# Mea_Vox_1_0a.net
KiCad netlist of a schematic drawn in EAGLE
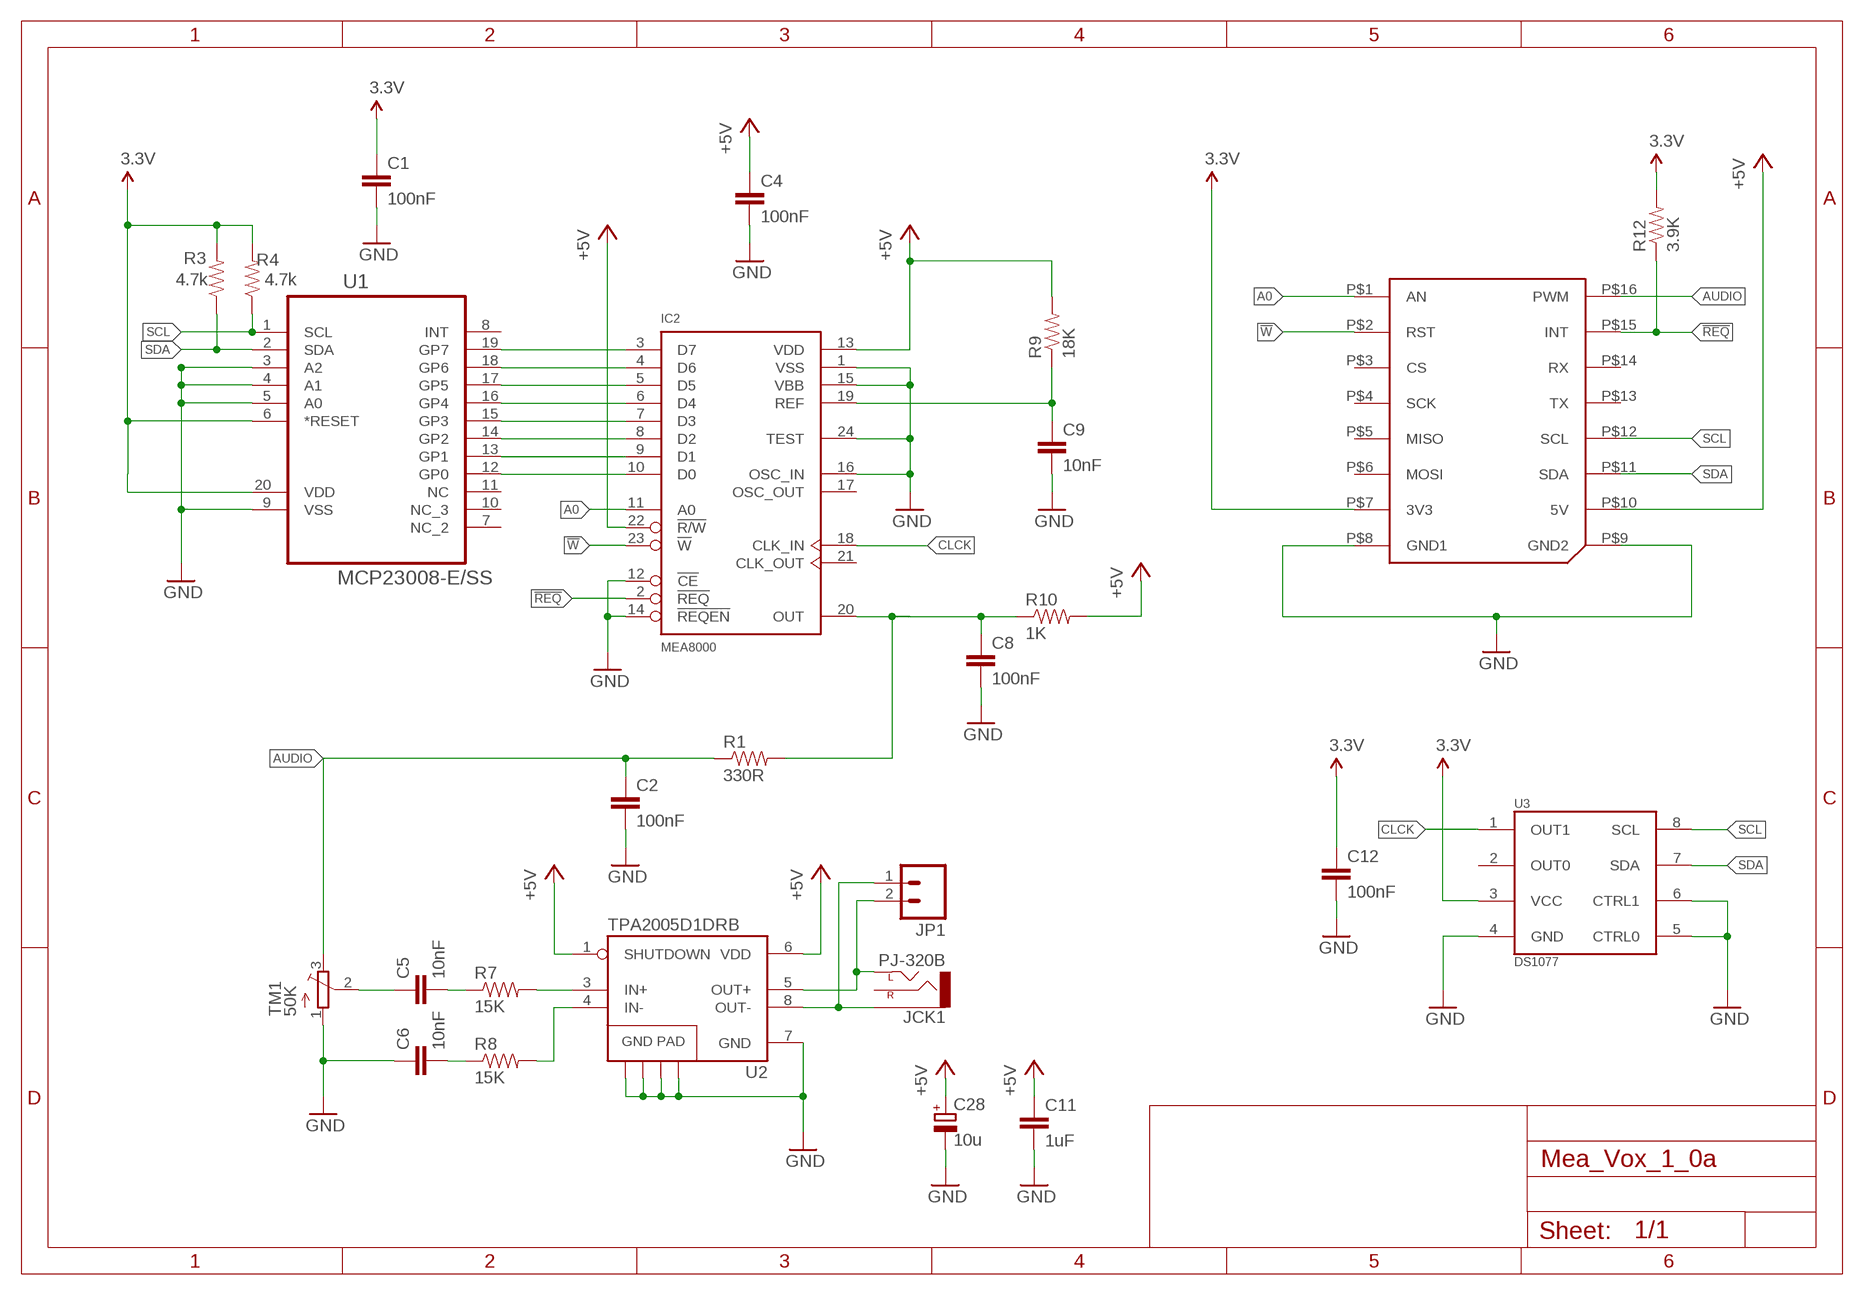
[diagram p0: schematic, sheet 1]

(export (version "E")
  (design (tool "Eeschema 10.0.6"))
  (components
    (comp (ref "C1")
      (value "100nF")
      (footprint "eagle-import:SPARKFUN_0805")
      (libsource (lib "eagle-import") (part "SPARKFUN_CAP0805"))
    )
    (comp (ref "C2")
      (value "100nF")
      (footprint "eagle-import:SPARKFUN_0805")
      (libsource (lib "eagle-import") (part "SPARKFUN_CAP0805"))
    )
    (comp (ref "C4")
      (value "100nF")
      (footprint "eagle-import:SPARKFUN_0805")
      (libsource (lib "eagle-import") (part "SPARKFUN_CAP0805"))
    )
    (comp (ref "C5")
      (value "10nF")
      (footprint "eagle-import:SPARKFUN_0805")
      (libsource (lib "eagle-import") (part "SPARKFUN_CAP0805"))
    )
    (comp (ref "C6")
      (value "10nF")
      (footprint "eagle-import:SPARKFUN_0805")
      (libsource (lib "eagle-import") (part "SPARKFUN_CAP0805"))
    )
    (comp (ref "C8")
      (value "100nF")
      (footprint "eagle-import:SPARKFUN_0805")
      (libsource (lib "eagle-import") (part "SPARKFUN_CAP0805"))
    )
    (comp (ref "C9")
      (value "10nF")
      (footprint "eagle-import:SPARKFUN_0805")
      (libsource (lib "eagle-import") (part "SPARKFUN_CAP0805"))
    )
    (comp (ref "C11")
      (value "1uF")
      (footprint "eagle-import:SPARKFUN_0805")
      (libsource (lib "eagle-import") (part "SPARKFUN_CAP0805"))
    )
    (comp (ref "C12")
      (value "100nF")
      (footprint "eagle-import:SPARKFUN_0805")
      (libsource (lib "eagle-import") (part "SPARKFUN_CAP0805"))
    )
    (comp (ref "C28")
      (value "10u")
      (footprint "eagle-import:A_3216-18R")
      (libsource (lib "eagle-import") (part "CPOL-EUA/3216-18R"))
    )
    (comp (ref "IC2")
      (value "MEA8000")
      (footprint "eagle-import:DIL24-6")
      (libsource (lib "eagle-import") (part "MEA8000"))
    )
    (comp (ref "JCK1")
      (value "PJ-320B")
      (footprint "eagle-import:FOOTPRINT")
      (libsource (lib "eagle-import") (part "PJ-320B"))
    )
    (comp (ref "JP1")
      (value "M02PTH")
      (footprint "eagle-import:1X02")
      (libsource (lib "eagle-import") (part "M02PTH"))
    )
    (comp (ref "MK1")
      (value "MIKROE_CLICKLARGE")
      (footprint "eagle-import:MIKROE_BUS_LARGE")
      (libsource (lib "eagle-import") (part "MIKROE_CLICKLARGE"))
    )
    (comp (ref "R1")
      (value "330R")
      (footprint "eagle-import:SPARKFUN_0805")
      (libsource (lib "eagle-import") (part "SPARKFUN_RESISTOR0805-RES"))
    )
    (comp (ref "R3")
      (value "4.7k")
      (footprint "eagle-import:SPARKFUN_0805")
      (libsource (lib "eagle-import") (part "SPARKFUN_RESISTOR0805-RES"))
    )
    (comp (ref "R4")
      (value "4.7k")
      (footprint "eagle-import:SPARKFUN_0805")
      (libsource (lib "eagle-import") (part "SPARKFUN_RESISTOR0805-RES"))
    )
    (comp (ref "R7")
      (value "15K")
      (footprint "eagle-import:SPARKFUN_0805")
      (libsource (lib "eagle-import") (part "SPARKFUN_RESISTOR0805-RES"))
    )
    (comp (ref "R8")
      (value "15K")
      (footprint "eagle-import:SPARKFUN_0805")
      (libsource (lib "eagle-import") (part "SPARKFUN_RESISTOR0805-RES"))
    )
    (comp (ref "R9")
      (value "18K")
      (footprint "eagle-import:SPARKFUN_0805")
      (libsource (lib "eagle-import") (part "SPARKFUN_RESISTOR0805-RES"))
    )
    (comp (ref "R10")
      (value "1K")
      (footprint "eagle-import:SPARKFUN_0805")
      (libsource (lib "eagle-import") (part "SPARKFUN_RESISTOR0805-RES"))
    )
    (comp (ref "R12")
      (value "3.9K")
      (footprint "eagle-import:SPARKFUN_0805")
      (libsource (lib "eagle-import") (part "SPARKFUN_RESISTOR0805-RES"))
    )
    (comp (ref "TM1")
      (value "50K")
      (footprint "eagle-import:TC33X")
      (libsource (lib "eagle-import") (part "TRIMPOTTC33X"))
    )
    (comp (ref "U1")
      (value "MCP23008-E/SS")
      (footprint "eagle-import:SOP65P780X200-20N")
      (libsource (lib "eagle-import") (part "MCP23008-E/SS"))
    )
    (comp (ref "U2")
      (value "TPA2005D1DRB")
      (footprint "eagle-import:QFN-8_PAD")
      (libsource (lib "eagle-import") (part "TPA2005D1DRB"))
    )
    (comp (ref "U3")
      (value "DS1077")
      (footprint "eagle-import:SO08")
      (libsource (lib "eagle-import") (part "DS1077"))
    )
  )
  (nets
    (net (code "1") (name "+5V") (class "Default")
      (node (ref "C11") (pin "1") (pinfunction "1_1") (pintype "passive"))
      (node (ref "C28") (pin "+") (pinfunction "+_+") (pintype "passive"))
      (node (ref "C4") (pin "1") (pinfunction "1_1") (pintype "passive"))
      (node (ref "IC2") (pin "13") (pinfunction "VDD_13") (pintype "power_in"))
      (node (ref "IC2") (pin "22") (pinfunction "~{R/W}_22") (pintype "input"))
      (node (ref "MK1") (pin "P$10") (pinfunction "5V_P$10") (pintype "bidirectional"))
      (node (ref "R10") (pin "2") (pinfunction "2_2") (pintype "passive"))
      (node (ref "R9") (pin "2") (pinfunction "2_2") (pintype "passive"))
      (node (ref "U2") (pin "1") (pinfunction "SHUTDOWN_1") (pintype "input"))
      (node (ref "U2") (pin "6") (pinfunction "VDD_6") (pintype "power_in"))
    )
    (net (code "2") (name "/~{REQ}") (class "Default")
      (node (ref "IC2") (pin "2") (pinfunction "~{REQ}_2") (pintype "input"))
      (node (ref "MK1") (pin "P$15") (pinfunction "INT_P$15") (pintype "bidirectional"))
      (node (ref "R12") (pin "1") (pinfunction "1_1") (pintype "passive"))
    )
    (net (code "3") (name "/~{W}") (class "Default")
      (node (ref "IC2") (pin "23") (pinfunction "~{W}_23") (pintype "input"))
      (node (ref "MK1") (pin "P$2") (pinfunction "RST_P$2") (pintype "bidirectional"))
    )
    (net (code "4") (name "3.3V") (class "Default")
      (node (ref "C1") (pin "1") (pinfunction "1_1") (pintype "passive"))
      (node (ref "C12") (pin "1") (pinfunction "1_1") (pintype "passive"))
      (node (ref "MK1") (pin "P$7") (pinfunction "3V3_P$7") (pintype "bidirectional"))
      (node (ref "R12") (pin "2") (pinfunction "2_2") (pintype "passive"))
      (node (ref "R3") (pin "2") (pinfunction "2_2") (pintype "passive"))
      (node (ref "R4") (pin "2") (pinfunction "2_2") (pintype "passive"))
      (node (ref "U1") (pin "20") (pinfunction "VDD_20") (pintype "power_in"))
      (node (ref "U1") (pin "6") (pinfunction "*RESET_6") (pintype "input"))
      (node (ref "U3") (pin "3") (pinfunction "VCC_3") (pintype "bidirectional"))
    )
    (net (code "5") (name "A0") (class "Default")
      (node (ref "IC2") (pin "11") (pinfunction "A0_11") (pintype "input"))
      (node (ref "MK1") (pin "P$1") (pinfunction "AN_P$1") (pintype "bidirectional"))
    )
    (net (code "6") (name "AUDIO") (class "Default")
      (node (ref "C2") (pin "1") (pinfunction "1_1") (pintype "passive"))
      (node (ref "MK1") (pin "P$16") (pinfunction "PWM_P$16") (pintype "bidirectional"))
      (node (ref "R1") (pin "1") (pinfunction "1_1") (pintype "passive"))
      (node (ref "TM1") (pin "3") (pinfunction "E_3") (pintype "passive"))
    )
    (net (code "7") (name "CLCK") (class "Default")
      (node (ref "IC2") (pin "18") (pinfunction "CLK_IN_18") (pintype "input"))
      (node (ref "U3") (pin "1") (pinfunction "OUT1_1") (pintype "bidirectional"))
    )
    (net (code "8") (name "GND") (class "Default")
      (node (ref "C1") (pin "2") (pinfunction "2_2") (pintype "passive"))
      (node (ref "C11") (pin "2") (pinfunction "2_2") (pintype "passive"))
      (node (ref "C12") (pin "2") (pinfunction "2_2") (pintype "passive"))
      (node (ref "C2") (pin "2") (pinfunction "2_2") (pintype "passive"))
      (node (ref "C28") (pin "-") (pinfunction "-_-") (pintype "passive"))
      (node (ref "C4") (pin "2") (pinfunction "2_2") (pintype "passive"))
      (node (ref "C6") (pin "1") (pinfunction "1_1") (pintype "passive"))
      (node (ref "C8") (pin "2") (pinfunction "2_2") (pintype "passive"))
      (node (ref "C9") (pin "2") (pinfunction "2_2") (pintype "passive"))
      (node (ref "IC2") (pin "1") (pinfunction "VSS_1") (pintype "power_in"))
      (node (ref "IC2") (pin "12") (pinfunction "~{CE}_12") (pintype "input"))
      (node (ref "IC2") (pin "14") (pinfunction "~{REQEN}_14") (pintype "input"))
      (node (ref "IC2") (pin "15") (pinfunction "VBB_15") (pintype "power_in"))
      (node (ref "IC2") (pin "16") (pinfunction "OSC_IN_16") (pintype "input"))
      (node (ref "IC2") (pin "24") (pinfunction "TEST_24") (pintype "bidirectional"))
      (node (ref "MK1") (pin "P$8") (pinfunction "GND1_P$8") (pintype "bidirectional"))
      (node (ref "MK1") (pin "P$9") (pinfunction "GND2_P$9") (pintype "bidirectional"))
      (node (ref "TM1") (pin "1") (pinfunction "A_1") (pintype "passive"))
      (node (ref "U1") (pin "3") (pinfunction "A2_3") (pintype "bidirectional"))
      (node (ref "U1") (pin "4") (pinfunction "A1_4") (pintype "input"))
      (node (ref "U1") (pin "5") (pinfunction "A0_5") (pintype "input"))
      (node (ref "U1") (pin "9") (pinfunction "VSS_9") (pintype "passive"))
      (node (ref "U2") (pin "10") (pinfunction "GND_10") (pintype "power_in"))
      (node (ref "U2") (pin "11") (pinfunction "GND_11") (pintype "power_in"))
      (node (ref "U2") (pin "12") (pinfunction "GND_12") (pintype "bidirectional"))
      (node (ref "U2") (pin "13") (pinfunction "GND_13") (pintype "bidirectional"))
      (node (ref "U2") (pin "7") (pinfunction "GND_7") (pintype "power_in"))
      (node (ref "U3") (pin "4") (pinfunction "GND_4") (pintype "bidirectional"))
      (node (ref "U3") (pin "5") (pinfunction "CTRL0_5") (pintype "bidirectional"))
      (node (ref "U3") (pin "6") (pinfunction "CTRL1_6") (pintype "bidirectional"))
    )
    (net (code "9") (name "Net-(C5-Pad2)") (class "Default")
      (node (ref "C5") (pin "2") (pinfunction "2_2") (pintype "passive"))
      (node (ref "R7") (pin "1") (pinfunction "1_1") (pintype "passive"))
    )
    (net (code "10") (name "Net-(C6-Pad2)") (class "Default")
      (node (ref "C6") (pin "2") (pinfunction "2_2") (pintype "passive"))
      (node (ref "R8") (pin "1") (pinfunction "1_1") (pintype "passive"))
    )
    (net (code "11") (name "Net-(IC2-D0)") (class "Default")
      (node (ref "IC2") (pin "10") (pinfunction "D0_10") (pintype "input"))
      (node (ref "U1") (pin "12") (pinfunction "GP0_12") (pintype "bidirectional"))
    )
    (net (code "12") (name "Net-(IC2-D1)") (class "Default")
      (node (ref "IC2") (pin "9") (pinfunction "D1_9") (pintype "input"))
      (node (ref "U1") (pin "13") (pinfunction "GP1_13") (pintype "bidirectional"))
    )
    (net (code "13") (name "Net-(IC2-D2)") (class "Default")
      (node (ref "IC2") (pin "8") (pinfunction "D2_8") (pintype "input"))
      (node (ref "U1") (pin "14") (pinfunction "GP2_14") (pintype "bidirectional"))
    )
    (net (code "14") (name "Net-(IC2-D3)") (class "Default")
      (node (ref "IC2") (pin "7") (pinfunction "D3_7") (pintype "input"))
      (node (ref "U1") (pin "15") (pinfunction "GP3_15") (pintype "bidirectional"))
    )
    (net (code "15") (name "Net-(IC2-D4)") (class "Default")
      (node (ref "IC2") (pin "6") (pinfunction "D4_6") (pintype "input"))
      (node (ref "U1") (pin "16") (pinfunction "GP4_16") (pintype "bidirectional"))
    )
    (net (code "16") (name "Net-(IC2-D5)") (class "Default")
      (node (ref "IC2") (pin "5") (pinfunction "D5_5") (pintype "input"))
      (node (ref "U1") (pin "17") (pinfunction "GP5_17") (pintype "bidirectional"))
    )
    (net (code "17") (name "Net-(IC2-D6)") (class "Default")
      (node (ref "IC2") (pin "4") (pinfunction "D6_4") (pintype "input"))
      (node (ref "U1") (pin "18") (pinfunction "GP6_18") (pintype "bidirectional"))
    )
    (net (code "18") (name "Net-(IC2-D7)") (class "Default")
      (node (ref "IC2") (pin "3") (pinfunction "D7_3") (pintype "input"))
      (node (ref "U1") (pin "19") (pinfunction "GP7_19") (pintype "bidirectional"))
    )
    (net (code "19") (name "Net-(IC2-OUT)") (class "Default")
      (node (ref "C8") (pin "1") (pinfunction "1_1") (pintype "passive"))
      (node (ref "IC2") (pin "20") (pinfunction "OUT_20") (pintype "output"))
      (node (ref "R1") (pin "2") (pinfunction "2_2") (pintype "passive"))
      (node (ref "R10") (pin "1") (pinfunction "1_1") (pintype "passive"))
    )
    (net (code "20") (name "Net-(IC2-REF)") (class "Default")
      (node (ref "C9") (pin "1") (pinfunction "1_1") (pintype "passive"))
      (node (ref "IC2") (pin "19") (pinfunction "REF_19") (pintype "input"))
      (node (ref "R9") (pin "1") (pinfunction "1_1") (pintype "passive"))
    )
    (net (code "21") (name "Net-(JCK1-LEFT)") (class "Default")
      (node (ref "JCK1") (pin "2") (pinfunction "LEFT_2") (pintype "bidirectional"))
      (node (ref "JP1") (pin "2") (pinfunction "2_2") (pintype "passive"))
      (node (ref "U2") (pin "5") (pinfunction "OUT+_5") (pintype "bidirectional"))
    )
    (net (code "22") (name "Net-(JCK1-SLEEVE)") (class "Default")
      (node (ref "JCK1") (pin "4") (pinfunction "SLEEVE_4") (pintype "bidirectional"))
      (node (ref "JP1") (pin "1") (pinfunction "1_1") (pintype "passive"))
      (node (ref "U2") (pin "8") (pinfunction "OUT-_8") (pintype "bidirectional"))
    )
    (net (code "23") (name "Net-(TM1-S)") (class "Default")
      (node (ref "C5") (pin "1") (pinfunction "1_1") (pintype "passive"))
      (node (ref "TM1") (pin "2") (pinfunction "S_2") (pintype "passive"))
    )
    (net (code "24") (name "Net-(U2-IN+)") (class "Default")
      (node (ref "R7") (pin "2") (pinfunction "2_2") (pintype "passive"))
      (node (ref "U2") (pin "3") (pinfunction "IN+_3") (pintype "bidirectional"))
    )
    (net (code "25") (name "Net-(U2-IN-)") (class "Default")
      (node (ref "R8") (pin "2") (pinfunction "2_2") (pintype "passive"))
      (node (ref "U2") (pin "4") (pinfunction "IN-_4") (pintype "bidirectional"))
    )
    (net (code "26") (name "SCL") (class "Default")
      (node (ref "MK1") (pin "P$12") (pinfunction "SCL_P$12") (pintype "bidirectional"))
      (node (ref "R4") (pin "1") (pinfunction "1_1") (pintype "passive"))
      (node (ref "U1") (pin "1") (pinfunction "SCL_1") (pintype "input"))
      (node (ref "U3") (pin "8") (pinfunction "SCL_8") (pintype "bidirectional"))
    )
    (net (code "27") (name "SDA") (class "Default")
      (node (ref "MK1") (pin "P$11") (pinfunction "SDA_P$11") (pintype "bidirectional"))
      (node (ref "R3") (pin "1") (pinfunction "1_1") (pintype "passive"))
      (node (ref "U1") (pin "2") (pinfunction "SDA_2") (pintype "bidirectional"))
      (node (ref "U3") (pin "7") (pinfunction "SDA_7") (pintype "bidirectional"))
    )
    (net (code "28") (name "unconnected-(IC2-CLK_OUT-Pad21)") (class "Default")
      (node (ref "IC2") (pin "21") (pinfunction "CLK_OUT_21") (pintype "output"))
    )
    (net (code "29") (name "unconnected-(IC2-OSC_OUT-Pad17)") (class "Default")
      (node (ref "IC2") (pin "17") (pinfunction "OSC_OUT_17") (pintype "output"))
    )
    (net (code "30") (name "unconnected-(JCK1-RIGHT-Pad3)") (class "Default")
      (node (ref "JCK1") (pin "3") (pinfunction "RIGHT_3") (pintype "bidirectional"))
    )
    (net (code "31") (name "unconnected-(MK1-CS-PadP$3)") (class "Default")
      (node (ref "MK1") (pin "P$3") (pinfunction "CS_P$3") (pintype "bidirectional"))
    )
    (net (code "32") (name "unconnected-(MK1-MISO-PadP$5)") (class "Default")
      (node (ref "MK1") (pin "P$5") (pinfunction "MISO_P$5") (pintype "bidirectional"))
    )
    (net (code "33") (name "unconnected-(MK1-MOSI-PadP$6)") (class "Default")
      (node (ref "MK1") (pin "P$6") (pinfunction "MOSI_P$6") (pintype "bidirectional"))
    )
    (net (code "34") (name "unconnected-(MK1-RX-PadP$14)") (class "Default")
      (node (ref "MK1") (pin "P$14") (pinfunction "RX_P$14") (pintype "bidirectional"))
    )
    (net (code "35") (name "unconnected-(MK1-SCK-PadP$4)") (class "Default")
      (node (ref "MK1") (pin "P$4") (pinfunction "SCK_P$4") (pintype "bidirectional"))
    )
    (net (code "36") (name "unconnected-(MK1-TX-PadP$13)") (class "Default")
      (node (ref "MK1") (pin "P$13") (pinfunction "TX_P$13") (pintype "bidirectional"))
    )
    (net (code "37") (name "unconnected-(U1-INT-Pad8)") (class "Default")
      (node (ref "U1") (pin "8") (pinfunction "INT_8") (pintype "output"))
    )
    (net (code "38") (name "unconnected-(U1-NC-Pad11)") (class "Default")
      (node (ref "U1") (pin "11") (pinfunction "NC_11") (pintype "no_connect"))
    )
    (net (code "39") (name "unconnected-(U1-NC_2-Pad7)") (class "Default")
      (node (ref "U1") (pin "7") (pinfunction "NC_2_7") (pintype "input"))
    )
    (net (code "40") (name "unconnected-(U1-NC_3-Pad10)") (class "Default")
      (node (ref "U1") (pin "10") (pinfunction "NC_3_10") (pintype "no_connect"))
    )
    (net (code "41") (name "unconnected-(U3-OUT0-Pad2)") (class "Default")
      (node (ref "U3") (pin "2") (pinfunction "OUT0_2") (pintype "bidirectional"))
    )
  )
)
